# RobotPower.net
KiCad netlist of a schematic drawn in Altium Designer
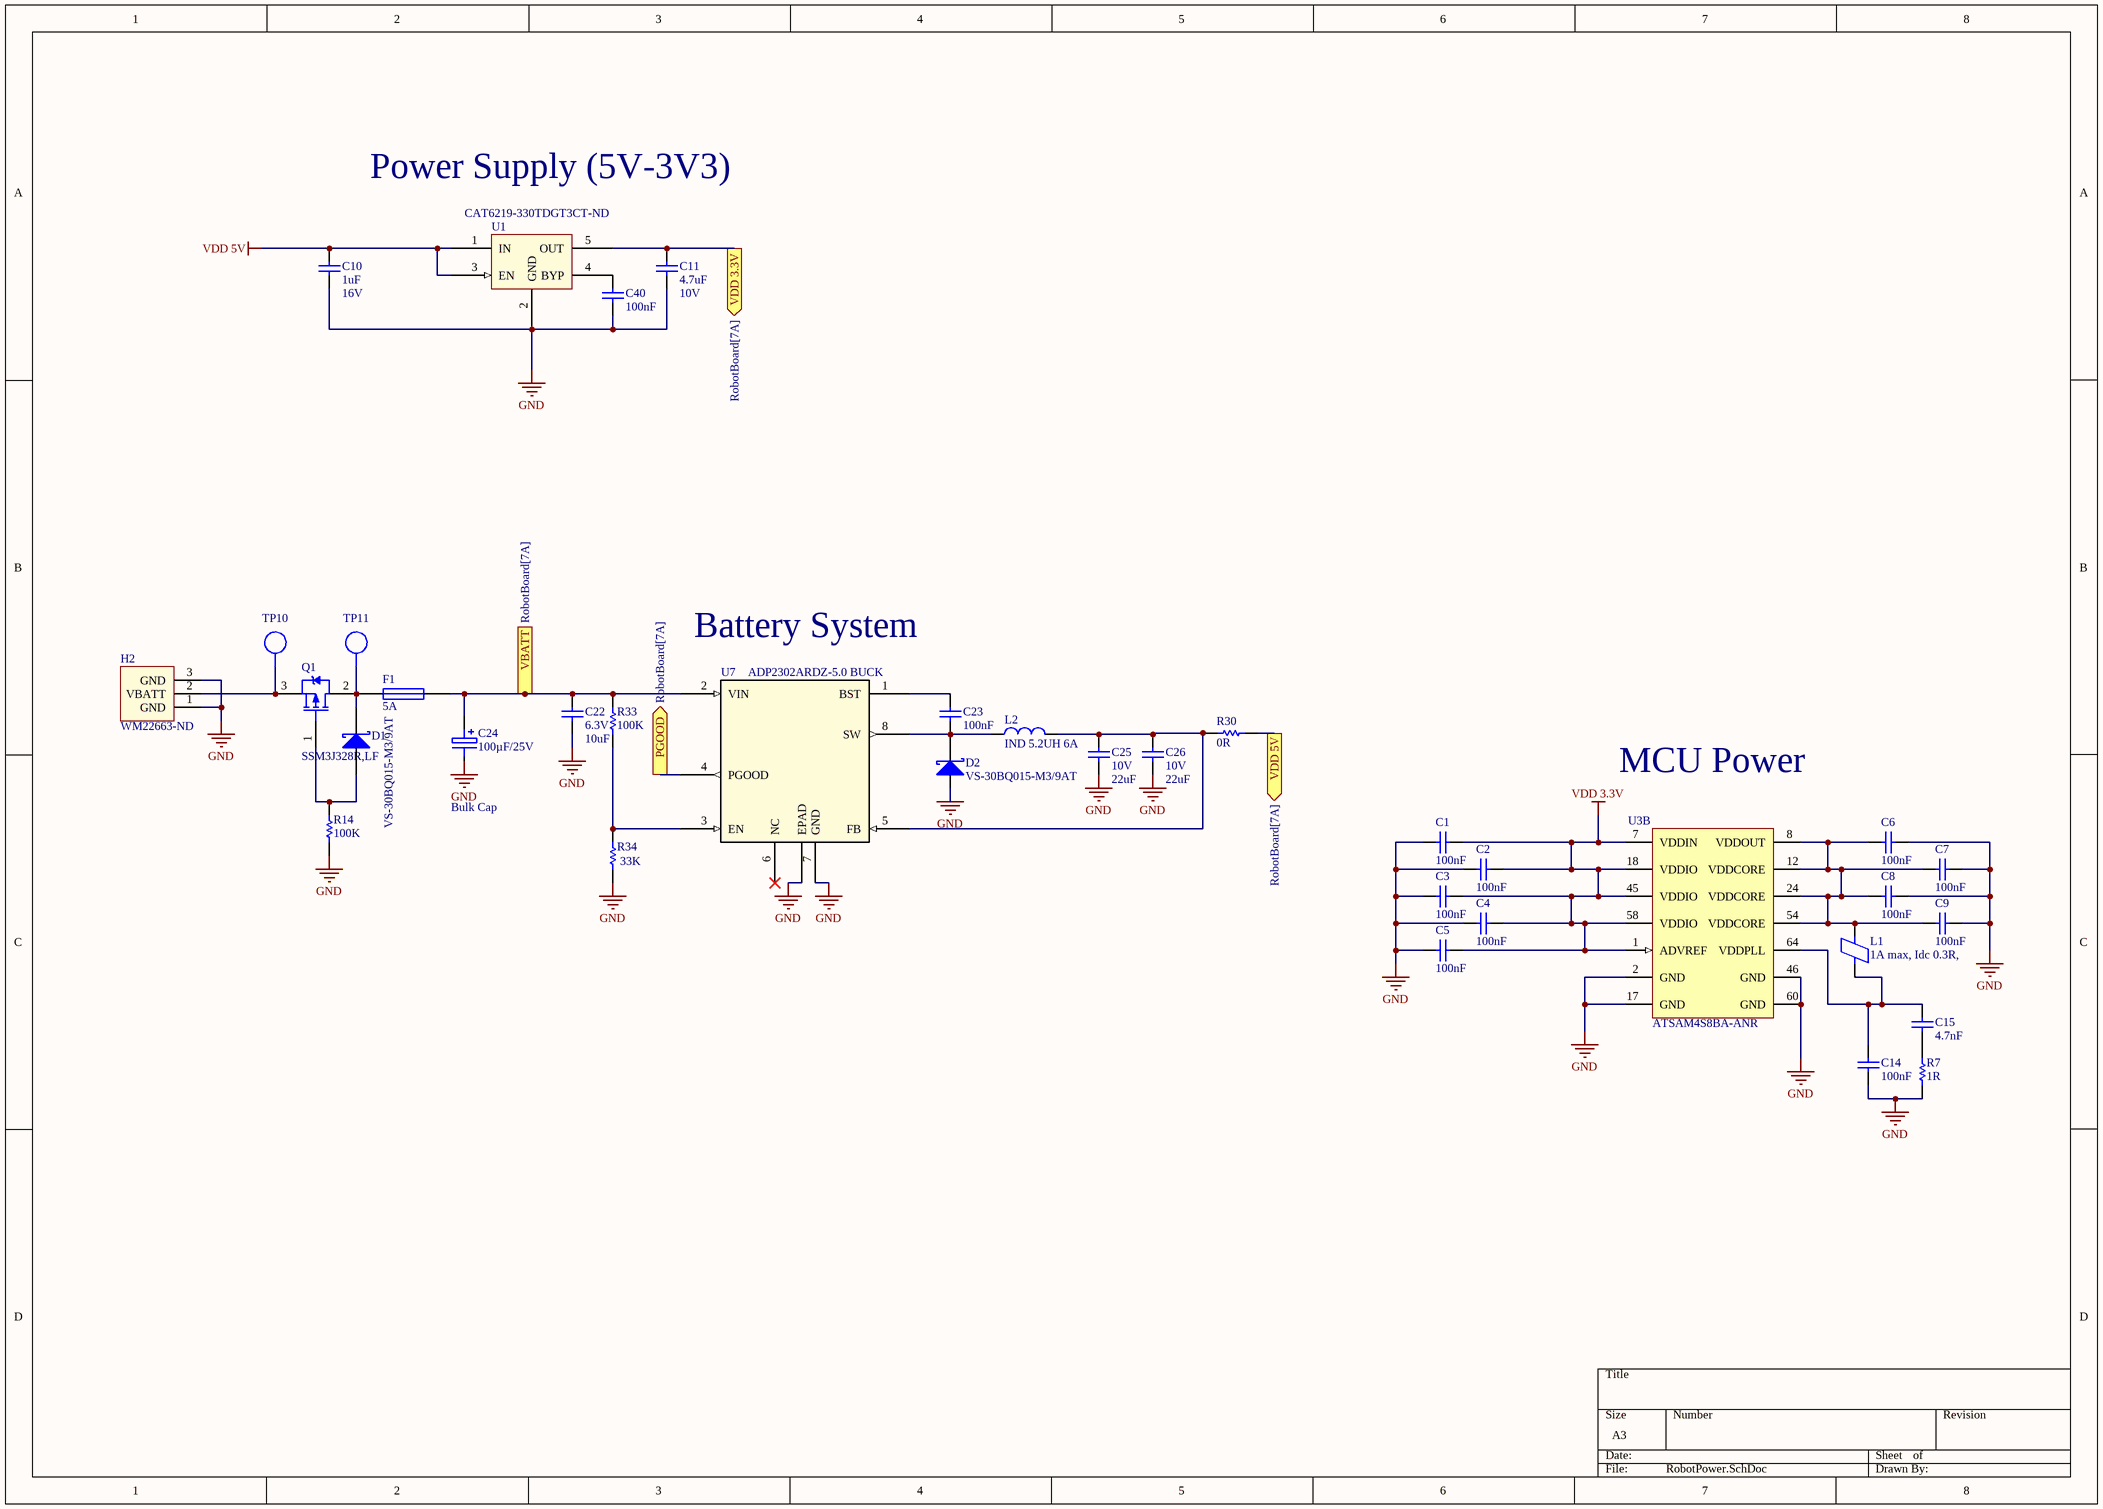
[diagram p0: RobotPower.SchDoc]

(export (version "E")
  (design (tool "Eeschema 10.0.6"))
  (components
    (comp (ref "C1")
      (value "100nF")
      (footprint "CAPC1608L")
      (description "CAP CER 100nF X7R +-10% 50V 0603")
      (libsource (lib "ECE_ComponentsAD23_2") (part "CC_100nF_0603"))
    )
    (comp (ref "C2")
      (value "100nF")
      (footprint "CAPC1608L")
      (description "CAP CER 100nF X7R +-10% 50V 0603")
      (libsource (lib "ECE_ComponentsAD23_2") (part "CC_100nF_0603"))
    )
    (comp (ref "C3")
      (value "100nF")
      (footprint "CAPC1608L")
      (description "CAP CER 100nF X7R +-10% 50V 0603")
      (libsource (lib "ECE_ComponentsAD23_2") (part "CC_100nF_0603"))
    )
    (comp (ref "C4")
      (value "100nF")
      (footprint "CAPC1608L")
      (description "CAP CER 100nF X7R +-10% 50V 0603")
      (libsource (lib "ECE_ComponentsAD23_2") (part "CC_100nF_0603"))
    )
    (comp (ref "C5")
      (value "100nF")
      (footprint "CAPC1608L")
      (description "CAP CER 100nF X7R +-10% 50V 0603")
      (libsource (lib "ECE_ComponentsAD23_2") (part "CC_100nF_0603"))
    )
    (comp (ref "C6")
      (value "100nF")
      (footprint "CAPC1608L")
      (description "CAP CER 100nF X7R +-10% 50V 0603")
      (libsource (lib "ECE_ComponentsAD23_2") (part "CC_100nF_0603"))
    )
    (comp (ref "C7")
      (value "100nF")
      (footprint "CAPC1608L")
      (description "CAP CER 100nF X7R +-10% 50V 0603")
      (libsource (lib "ECE_ComponentsAD23_2") (part "CC_100nF_0603"))
    )
    (comp (ref "C8")
      (value "100nF")
      (footprint "CAPC1608L")
      (description "CAP CER 100nF X7R +-10% 50V 0603")
      (libsource (lib "ECE_ComponentsAD23_2") (part "CC_100nF_0603"))
    )
    (comp (ref "C9")
      (value "100nF")
      (footprint "CAPC1608L")
      (description "CAP CER 100nF X7R +-10% 50V 0603")
      (libsource (lib "ECE_ComponentsAD23_2") (part "CC_100nF_0603"))
    )
    (comp (ref "C10")
      (value "1uF")
      (footprint "CAPC1608L")
      (description "CAP CER 1uF Y5V -20% +80% 16V 0603")
      (fields (field (name "MAX VOLTAGE") "16V"))
      (libsource (lib "ECE_ComponentsAD23_2") (part "CC_1uF_0603"))
    )
    (comp (ref "C11")
      (value "4.7uF")
      (footprint "CAPC1608N")
      (description "CAP CER 4.7uF X5R +-20%  10V 0603")
      (fields (field (name "MAX VOLTAGE") "10V"))
      (libsource (lib "ECE_ComponentsAD23_2") (part "CC_4.7uF_0603"))
    )
    (comp (ref "C14")
      (value "100nF")
      (footprint "CAPC1608L")
      (description "CAP CER 100nF X7R +-10% 50V 0603")
      (libsource (lib "ECE_ComponentsAD23_2") (part "CC_100nF_0603"))
    )
    (comp (ref "C15")
      (value "4.7nF")
      (footprint "CAPC1608L")
      (description "CAP CER 4.7nF X7R +-10% 50V 0603")
      (libsource (lib "ECE_ComponentsAD23_2") (part "CC_4.7nF_0603"))
    )
    (comp (ref "C22")
      (value "10uF")
      (footprint "CAPC1608L")
      (description "CAP CER 10UF X5R +-20% 6V3 0603")
      (fields (field (name "VOLTAGE - RATED") "6.3V"))
      (libsource (lib "ECE_ComponentsAD23_2") (part "CC_10uF_0603"))
    )
    (comp (ref "C23")
      (value "100nF")
      (footprint "CAPC1608L")
      (description "CAP CER 100nF X7R +-10% 50V 0603")
      (libsource (lib "ECE_ComponentsAD23_2") (part "CC_100nF_0603"))
    )
    (comp (ref "C24")
      (value "100µF/25V")
      (footprint "CAPAE6666X77M")
      (description "CAP ALUM 100UF 25V 20% SMD")
      (fields
        (field (name "MANUFACTURER") "Nichicon")
        (field (name "MANUFACTURER PART NUMBER") "UWT1E101MCL1GS")
        (field (name "CAPACITANCE") "100µF/25V")
      )
      (libsource (lib "ECE_ComponentsAD23_2") (part "CA_100uF_25V"))
    )
    (comp (ref "C25")
      (value "22uF")
      (footprint "CAPC3216L")
      (description "CAP CER 22uF Y5V -20% +80% 10V 1206")
      (fields (field (name "MAX VOLTAGE") "10V"))
      (libsource (lib "ECE_ComponentsAD23_2") (part "CC_22uF_1206"))
    )
    (comp (ref "C26")
      (value "22uF")
      (footprint "CAPC3216L")
      (description "CAP CER 22uF Y5V -20% +80% 10V 1206")
      (fields (field (name "MAX VOLTAGE") "10V"))
      (libsource (lib "ECE_ComponentsAD23_2") (part "CC_22uF_1206"))
    )
    (comp (ref "C40")
      (value "100nF")
      (footprint "CAPC1608L")
      (description "CAP CER 10nF X7R +-10% 50V 0603")
      (fields (field (name "Comment") "10nF"))
      (libsource (lib "ECE_ComponentsAD23_2") (part "CC_10nF_0603"))
    )
    (comp (ref "D1")
      (value "VS-30BQ015-M3/9AT")
      (footprint "SMC")
      (description "DIODE, SCHOTTKY, 3A, 15V, DO-214AB / SMC")
      (fields (field (name "MANUFACTURER") "Vishay Semiconductors"))
      (libsource (lib "ECE_ComponentsAD23_2") (part "DS_VS-30BQ015-M3"))
    )
    (comp (ref "D2")
      (value "VS-30BQ015-M3/9AT")
      (footprint "SMC")
      (description "DIODE, SCHOTTKY, 3A, 15V, DO-214AB / SMC")
      (fields (field (name "MANUFACTURER") "Vishay Semiconductors"))
      (libsource (lib "ECE_ComponentsAD23_2") (part "DS_VS-30BQ015-M3"))
    )
    (comp (ref "F1")
      (value "5A")
      (footprint "RESC3216N")
      (description "Fuse 5.0A Fast Acting 1206 SMD")
      (fields (field (name "MANUFACTURER PART NUMBER") "C1F5") (field (name "MANUFACTURER") "Bel TRP"))
      (libsource (lib "ECE_ComponentsAD23_2") (part "FS_Fuse_5.0A"))
    )
    (comp (ref "H2")
      (value "Battery_HEADER_3pin")
      (footprint "BATT_HEADER_3POS")
      (description "3Pin Header 2.54mm spacing\r\nDigikey #WM22663-ND")
      (fields (field (name "SUPPLIER PART NUMBER 1") "WM22663-ND"))
      (libsource (lib "ENCE461AD23") (part "Battery_HEADER_3pin"))
    )
    (comp (ref "L1")
      (value "1A max, Idc 0.3R,")
      (footprint "INDC3216L")
      (description "Ferrite Bead, Rdc 0.3R, Z100MHZ 600R, Imax 1A, SMD 1206")
      (fields
        (field (name "MANUFACTURER") "FAIR-RITE")
        (field (name "MANUFACTURER PART NUMBER") "2512066017Y1")
      )
      (libsource (lib "ECE_ComponentsAD23_2") (part "IN_Ferrite-Bead"))
    )
    (comp (ref "L2")
      (value "IND 5.2UH 6A")
      (footprint "INDUCTOR5u2")
      (description "FIXED IND 5.2UH 6A 22 MOHM SMD")
      (fields
        (field (name "MANUFACTURER") "Sumida America Components Inc.")
        (field (name "MANUFACTURER PART NUMBER") "CDRH104RNP-5R2NC")
      )
      (libsource (lib "ENCE461AD23") (part "CDRH104RNP-5R2NC"))
    )
    (comp (ref "Q1")
      (value "SSM3J328R,LF")
      (footprint "SOT23_L")
      (description "MOSFET P-CH 20V 6A SOT23-3")
      (fields
        (field (name "MANUFACTURER") "Toshiba")
        (field (name "MANUFACTURER PART NUMBER") "SSM3J328R,LF")
      )
      (libsource (lib "ECE_ComponentsAD23_2") (part "TM_SSM3J328R"))
    )
    (comp (ref "R7")
      (value "1R")
      (footprint "RESC1608L")
      (description "RES 1.0K OHM 1/10W 5% 0603 SMD")
      (libsource (lib "ECE_ComponentsAD23_2") (part "RS_1K"))
    )
    (comp (ref "R14")
      (value "100K")
      (footprint "RESC1608L")
      (description "RES 100K OHM 1/10W 5% 0603 SMD")
      (libsource (lib "ECE_ComponentsAD23_2") (part "RS_100K"))
    )
    (comp (ref "R30")
      (value "0R")
      (footprint "RESC1608L")
      (description "RES 0.0 OHM 1/10W 5% 0603 SMD")
      (libsource (lib "ECE_ComponentsAD23_2") (part "RS_0R0"))
    )
    (comp (ref "R33")
      (value "100K")
      (footprint "RESC1608L")
      (description "RES 100K OHM 1/10W 5% 0603 SMD")
      (libsource (lib "ECE_ComponentsAD23_2") (part "RS_100K"))
    )
    (comp (ref "R34")
      (value "33K")
      (footprint "RESC1608L")
      (description "RES 33.0K OHM 1/10W 5% 0603 SMD")
      (libsource (lib "ECE_ComponentsAD23_2") (part "RS_33K"))
    )
    (comp (ref "TP10")
      (value "TP")
      (footprint "TP_1206")
      (description "Test-Point 3.3x1.6x2.1mm SMD")
      (fields
        (field (name "MANUFACTURER") "Harwin Inc")
        (field (name "MANUFACTURER PART NUMBER") "S1751-46R")
      )
      (libsource (lib "ECE_ComponentsAD23_2") (part "TP_1206"))
    )
    (comp (ref "TP11")
      (value "TP")
      (footprint "TP_1206")
      (description "Test-Point 3.3x1.6x2.1mm SMD")
      (fields
        (field (name "MANUFACTURER") "Harwin Inc")
        (field (name "MANUFACTURER PART NUMBER") "S1751-46R")
      )
      (libsource (lib "ECE_ComponentsAD23_2") (part "TP_1206"))
    )
    (comp (ref "U1")
      (value "CAT6219-330TDGT3")
      (footprint "SOT95P280X145-5N")
      (description "IC REG LIN 3.3V 500MA TSOT23-5")
      (fields
        (field (name "BASE PART NUMBER") "CAT6219")
        (field (name "SUPPLIER PART NUMBER") "CAT6219-330TDGT3CT-ND")
      )
      (libsource (lib "ENCE461AD23") (part "SV_CAT6219-330TDGT3"))
    )
    (comp (ref "U3")
      (value "ATSAM4S8BA-ANR")
      (footprint "LQFP64_L")
      (description "IC MCU 32BIT 512KB FLASH 64LQFP")
      (fields (field (name "MANUFACTURER") "Atmel"))
      (libsource (lib "ECE_ComponentsAD23_2") (part "SE_ATSAM4S16BA-MU"))
    )
    (comp (ref "U7")
      (value "ADP2302ARDZ-5.0 BUCK")
      (footprint "RD_8_1")
      (description "IC REG BUCK 5V 2A 8SOIC")
      (fields (field (name "MANUFACTURER_PART_NUMBER") "ADP2302ARDZ-5.0-R7"))
      (libsource (lib "ENCE461AD23") (part "ADP2302ARDZ-5.0-R7"))
    )
  )
  (nets
    (net (code "1") (name "/PGOOD") (class "Default")
      (node (ref "U7") (pin "4") (pinfunction "PGOOD_4") (pintype "output"))
    )
    (net (code "2") (name "/VBATT") (class "Default")
      (node (ref "C22") (pin "1") (pinfunction "1_1") (pintype "passive"))
      (node (ref "C24") (pin "2") (pintype "passive"))
      (node (ref "F1") (pin "2") (pinfunction "2_2") (pintype "passive"))
      (node (ref "R33") (pin "1") (pinfunction "1_1") (pintype "passive"))
      (node (ref "U7") (pin "2") (pinfunction "VIN_2") (pintype "input"))
    )
    (net (code "3") (name "GND") (class "Default")
      (node (ref "C1") (pin "1") (pinfunction "1_1") (pintype "passive"))
      (node (ref "C10") (pin "2") (pinfunction "2_2") (pintype "passive"))
      (node (ref "C11") (pin "2") (pinfunction "2_2") (pintype "passive"))
      (node (ref "C14") (pin "2") (pinfunction "2_2") (pintype "passive"))
      (node (ref "C2") (pin "1") (pinfunction "1_1") (pintype "passive"))
      (node (ref "C22") (pin "2") (pinfunction "2_2") (pintype "passive"))
      (node (ref "C24") (pin "1") (pintype "passive"))
      (node (ref "C25") (pin "2") (pinfunction "2_2") (pintype "passive"))
      (node (ref "C26") (pin "2") (pinfunction "2_2") (pintype "passive"))
      (node (ref "C3") (pin "1") (pinfunction "1_1") (pintype "passive"))
      (node (ref "C4") (pin "1") (pinfunction "1_1") (pintype "passive"))
      (node (ref "C40") (pin "1") (pinfunction "1_1") (pintype "passive"))
      (node (ref "C5") (pin "1") (pinfunction "1_1") (pintype "passive"))
      (node (ref "C6") (pin "2") (pinfunction "2_2") (pintype "passive"))
      (node (ref "C7") (pin "2") (pinfunction "2_2") (pintype "passive"))
      (node (ref "C8") (pin "2") (pinfunction "2_2") (pintype "passive"))
      (node (ref "C9") (pin "2") (pinfunction "2_2") (pintype "passive"))
      (node (ref "D2") (pin "1") (pinfunction "A_1") (pintype "passive"))
      (node (ref "H2") (pin "1") (pinfunction "GND_1") (pintype "passive"))
      (node (ref "H2") (pin "3") (pinfunction "GND_3") (pintype "passive"))
      (node (ref "R14") (pin "2") (pinfunction "2_2") (pintype "passive"))
      (node (ref "R34") (pin "2") (pinfunction "2_2") (pintype "passive"))
      (node (ref "R7") (pin "2") (pinfunction "2_2") (pintype "passive"))
      (node (ref "U1") (pin "2") (pinfunction "GND_2") (pintype "power_in"))
      (node (ref "U3") (pin "17") (pinfunction "GND_17") (pintype "power_in"))
      (node (ref "U3") (pin "2") (pinfunction "GND_2") (pintype "power_in"))
      (node (ref "U3") (pin "46") (pinfunction "GND_46") (pintype "power_in"))
      (node (ref "U3") (pin "60") (pinfunction "GND_60") (pintype "power_in"))
      (node (ref "U7") (pin "7") (pinfunction "GND_7") (pintype "power_in"))
      (node (ref "U7") (pin "EPAD") (pinfunction "EPAD_EPAD") (pintype "passive"))
    )
    (net (code "4") (name "Net-(C15-Pad2)") (class "Default")
      (node (ref "C15") (pin "2") (pinfunction "2_2") (pintype "passive"))
      (node (ref "R7") (pin "1") (pinfunction "1_1") (pintype "passive"))
    )
    (net (code "5") (name "Net-(D1-A)") (class "Default")
      (node (ref "D1") (pin "1") (pinfunction "A_1") (pintype "passive"))
      (node (ref "Q1") (pin "1") (pinfunction "1_1") (pintype "passive"))
      (node (ref "R14") (pin "1") (pinfunction "1_1") (pintype "passive"))
    )
    (net (code "6") (name "Net-(D1-K)") (class "Default")
      (node (ref "D1") (pin "2") (pinfunction "K_2") (pintype "passive"))
      (node (ref "F1") (pin "1") (pinfunction "1_1") (pintype "passive"))
      (node (ref "Q1") (pin "2") (pinfunction "2_2") (pintype "passive"))
      (node (ref "TP11") (pin "1") (pinfunction "1_1") (pintype "passive"))
    )
    (net (code "7") (name "Net-(D2-K)") (class "Default")
      (node (ref "C23") (pin "2") (pinfunction "2_2") (pintype "passive"))
      (node (ref "D2") (pin "2") (pinfunction "K_2") (pintype "passive"))
      (node (ref "L2") (pin "1") (pintype "passive"))
      (node (ref "U7") (pin "8") (pinfunction "SW_8") (pintype "output"))
    )
    (net (code "8") (name "Net-(H2-VBATT)") (class "Default")
      (node (ref "H2") (pin "2") (pinfunction "VBATT_2") (pintype "passive"))
      (node (ref "Q1") (pin "3") (pinfunction "3_3") (pintype "passive"))
      (node (ref "TP10") (pin "1") (pinfunction "1_1") (pintype "passive"))
    )
    (net (code "9") (name "Net-(U1-BYP)") (class "Default")
      (node (ref "C40") (pin "2") (pinfunction "2_2") (pintype "passive"))
      (node (ref "U1") (pin "4") (pinfunction "BYP_4") (pintype "passive"))
    )
    (net (code "10") (name "Net-(U3B-VDDOUT)") (class "Default")
      (node (ref "C6") (pin "1") (pinfunction "1_1") (pintype "passive"))
      (node (ref "C7") (pin "1") (pinfunction "1_1") (pintype "passive"))
      (node (ref "C8") (pin "1") (pinfunction "1_1") (pintype "passive"))
      (node (ref "C9") (pin "1") (pinfunction "1_1") (pintype "passive"))
      (node (ref "L1") (pin "1") (pinfunction "1_1") (pintype "passive"))
      (node (ref "U3") (pin "12") (pinfunction "VDDCORE_12") (pintype "power_in"))
      (node (ref "U3") (pin "24") (pinfunction "VDDCORE_24") (pintype "power_in"))
      (node (ref "U3") (pin "54") (pinfunction "VDDCORE_54") (pintype "power_in"))
      (node (ref "U3") (pin "8") (pinfunction "VDDOUT_8") (pintype "power_in"))
    )
    (net (code "11") (name "Net-(U3B-VDDPLL)") (class "Default")
      (node (ref "C14") (pin "1") (pinfunction "1_1") (pintype "passive"))
      (node (ref "C15") (pin "1") (pinfunction "1_1") (pintype "passive"))
      (node (ref "L1") (pin "2") (pinfunction "2_2") (pintype "passive"))
      (node (ref "U3") (pin "64") (pinfunction "VDDPLL_64") (pintype "power_in"))
    )
    (net (code "12") (name "Net-(U7-BST)") (class "Default")
      (node (ref "C23") (pin "1") (pinfunction "1_1") (pintype "passive"))
      (node (ref "U7") (pin "1") (pinfunction "BST_1") (pintype "passive"))
    )
    (net (code "13") (name "Net-(U7-EN)") (class "Default")
      (node (ref "R33") (pin "2") (pinfunction "2_2") (pintype "passive"))
      (node (ref "R34") (pin "1") (pinfunction "1_1") (pintype "passive"))
      (node (ref "U7") (pin "3") (pinfunction "EN_3") (pintype "input"))
    )
    (net (code "14") (name "Net-(U7-FB)") (class "Default")
      (node (ref "C25") (pin "1") (pinfunction "1_1") (pintype "passive"))
      (node (ref "C26") (pin "1") (pinfunction "1_1") (pintype "passive"))
      (node (ref "L2") (pin "2") (pintype "passive"))
      (node (ref "R30") (pin "1") (pinfunction "1_1") (pintype "passive"))
      (node (ref "U7") (pin "5") (pinfunction "FB_5") (pintype "input"))
    )
    (net (code "15") (name "VDD 3.3V") (class "Default")
      (node (ref "C1") (pin "2") (pinfunction "2_2") (pintype "passive"))
      (node (ref "C11") (pin "1") (pinfunction "1_1") (pintype "passive"))
      (node (ref "C2") (pin "2") (pinfunction "2_2") (pintype "passive"))
      (node (ref "C3") (pin "2") (pinfunction "2_2") (pintype "passive"))
      (node (ref "C4") (pin "2") (pinfunction "2_2") (pintype "passive"))
      (node (ref "C5") (pin "2") (pinfunction "2_2") (pintype "passive"))
      (node (ref "U1") (pin "5") (pinfunction "OUT_5") (pintype "power_in"))
      (node (ref "U3") (pin "1") (pinfunction "ADVREF_1") (pintype "input"))
      (node (ref "U3") (pin "18") (pinfunction "VDDIO_18") (pintype "power_in"))
      (node (ref "U3") (pin "45") (pinfunction "VDDIO_45") (pintype "power_in"))
      (node (ref "U3") (pin "58") (pinfunction "VDDIO_58") (pintype "power_in"))
      (node (ref "U3") (pin "7") (pinfunction "VDDIN_7") (pintype "power_in"))
    )
    (net (code "16") (name "VDD 5V") (class "Default")
      (node (ref "C10") (pin "1") (pinfunction "1_1") (pintype "passive"))
      (node (ref "R30") (pin "2") (pinfunction "2_2") (pintype "passive"))
      (node (ref "U1") (pin "1") (pinfunction "IN_1") (pintype "power_in"))
      (node (ref "U1") (pin "3") (pinfunction "EN_3") (pintype "input"))
    )
    (net (code "17") (name "unconnected-(U7-NC-Pad6)") (class "Default")
      (node (ref "U7") (pin "6") (pinfunction "NC_6") (pintype "passive+no_connect"))
    )
  )
)
